# 01_Power.net
KiCad netlist of a schematic drawn in Altium Designer
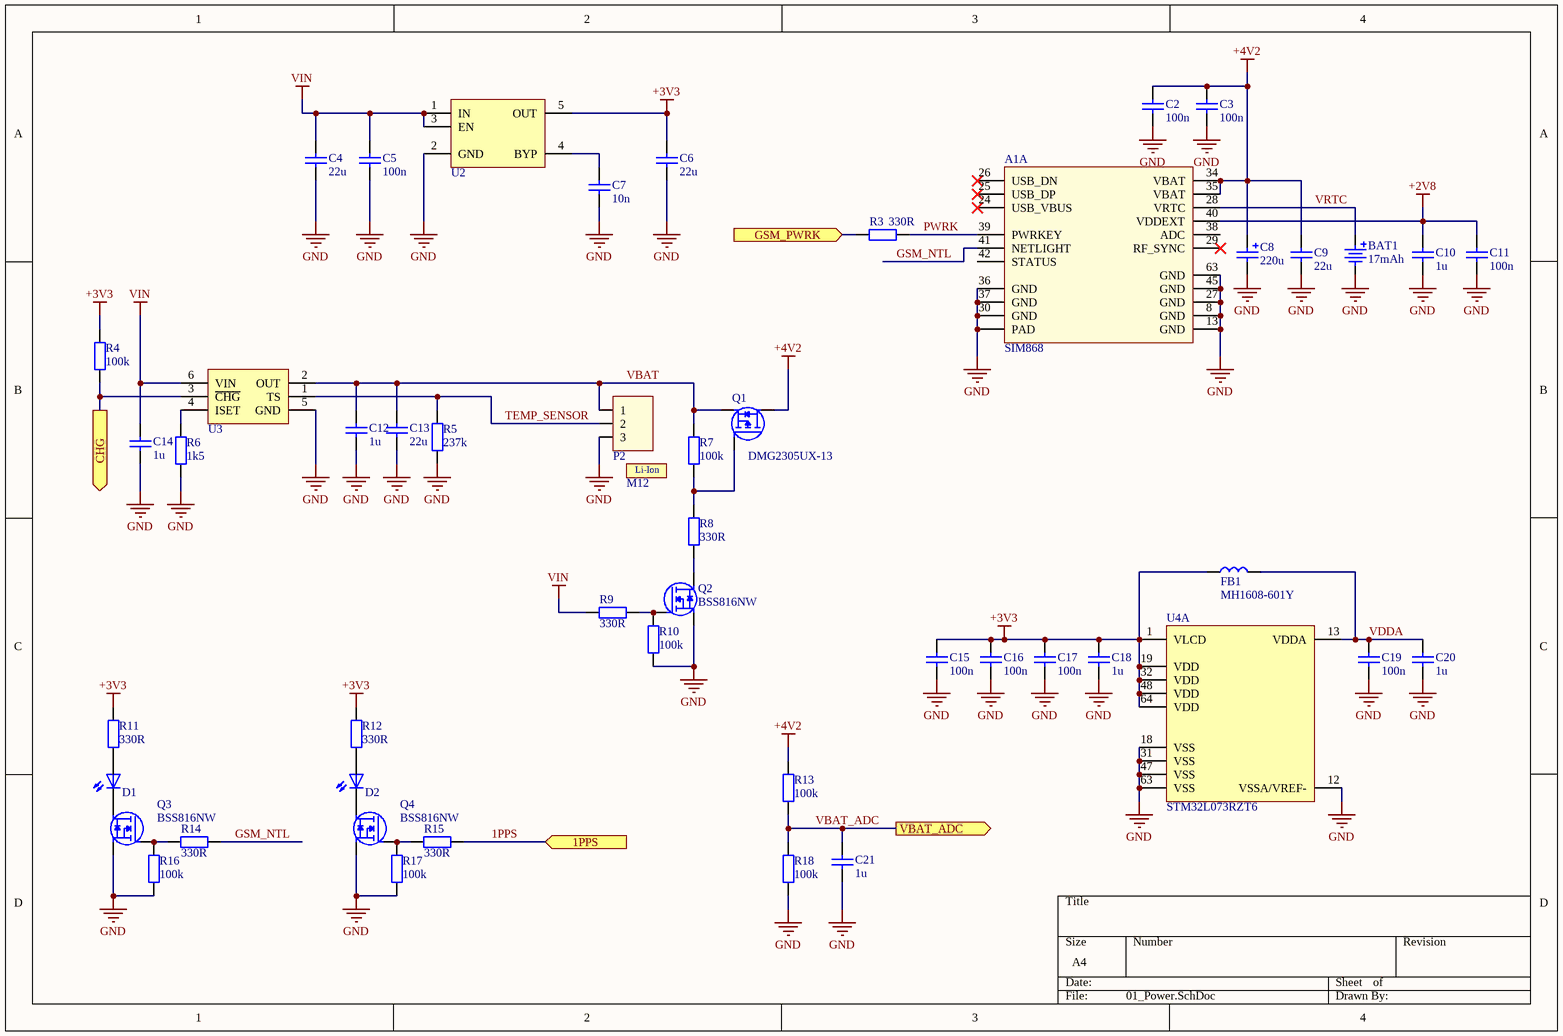
[diagram p0: 01_Power.SchDoc]

(export (version "E")
  (design (tool "Eeschema 10.0.6"))
  (components
    (comp (ref "A1")
      (value "SIM868")
      (footprint "SIM868")
      (description "GSM & GPRS & GPS Modules PCBModule RoHS")
      (fields (field (name "MANUFACTURER") "SIMCom Wireless Solutions"))
      (libsource (lib "alfasat_lib") (part "SIM868"))
    )
    (comp (ref "BAT1")
      (value "17mAh")
      (footprint "ML1220")
      (description "BATT LITH 3V 17MAH COIN 12.5MM")
      (fields (field (name "MANUFACTURER") "China") (field (name "MANUFACTURER PART NUMBER") "ML1220"))
      (libsource (lib "alfasat_lib") (part "ML1220"))
    )
    (comp (ref "C2")
      (value "100n")
      (footprint "C0603_IPC_MD")
      (description "CAP CER 0.1UF 16V X7R 0603")
      (fields
        (field (name "MANUFACTURER") "Samsung Electro-Mechanics")
        (field (name "MANUFACTURER PART NUMBER") "CL10B104KO8NNNC")
      )
      (libsource (lib "alfasat_lib") (part "CL10B104KO8NNNC"))
    )
    (comp (ref "C3")
      (value "100n")
      (footprint "C0603_IPC_MD")
      (description "CAP CER 0.1UF 16V X7R 0603")
      (fields
        (field (name "MANUFACTURER") "Samsung Electro-Mechanics")
        (field (name "MANUFACTURER PART NUMBER") "CL10B104KO8NNNC")
      )
      (libsource (lib "alfasat_lib") (part "CL10B104KO8NNNC"))
    )
    (comp (ref "C4")
      (value "22u")
      (footprint "C0805_IPC_HD")
      (description "CAP CER 22UF 16V X5R 0805")
      (fields
        (field (name "MANUFACTURER") "Samsung Electro-Mechanics")
        (field (name "MANUFACTURER PART NUMBER") "CL21A226MOCLRNC")
      )
      (libsource (lib "alfasat_lib") (part "CL21A226MOCLRNC"))
    )
    (comp (ref "C5")
      (value "100n")
      (footprint "C0603_IPC_MD")
      (description "CAP CER 0.1UF 16V X7R 0603")
      (fields
        (field (name "MANUFACTURER") "Samsung Electro-Mechanics")
        (field (name "MANUFACTURER PART NUMBER") "CL10B104KO8NNNC")
      )
      (libsource (lib "alfasat_lib") (part "CL10B104KO8NNNC"))
    )
    (comp (ref "C6")
      (value "22u")
      (footprint "C0805_IPC_HD")
      (description "CAP CER 22UF 16V X5R 0805")
      (fields
        (field (name "MANUFACTURER") "Samsung Electro-Mechanics")
        (field (name "MANUFACTURER PART NUMBER") "CL21A226MOCLRNC")
      )
      (libsource (lib "alfasat_lib") (part "CL21A226MOCLRNC"))
    )
    (comp (ref "C7")
      (value "10n")
      (footprint "C0603_IPC_MD")
      (description "CAP CER 0.01UF 50V X7R 0603")
      (fields
        (field (name "MANUFACTURER") "Samsung Electro-Mechanics")
        (field (name "MANUFACTURER PART NUMBER") "CL10B103KB8NNNC")
      )
      (libsource (lib "alfasat_lib") (part "CL10B103KB8NNNC"))
    )
    (comp (ref "C8")
      (value "220u")
      (footprint "TANT_CAP_7343")
      (description "Tantalum Capacitors 220uF 6.3V CASE-D_7343 RoHS")
      (fields (field (name "MANUFACTURER") "PANASONIC") (field (name "MANUFACTURER PART NUMBER") "6TPE220MI"))
      (libsource (lib "alfasat_lib") (part "6TPE220MI"))
    )
    (comp (ref "C9")
      (value "22u")
      (footprint "C0805_IPC_HD")
      (description "CAP CER 22UF 16V X5R 0805")
      (fields
        (field (name "MANUFACTURER") "Samsung Electro-Mechanics")
        (field (name "MANUFACTURER PART NUMBER") "CL21A226MOCLRNC")
      )
      (libsource (lib "alfasat_lib") (part "CL21A226MOCLRNC"))
    )
    (comp (ref "C10")
      (value "1u")
      (footprint "C0603_IPC_MD")
      (description "CAP CER 1UF 16V X7R 0603")
      (fields
        (field (name "MANUFACTURER") "Samsung Electro-Mechanics")
        (field (name "MANUFACTURER PART NUMBER") "CL10B105MO8NNWC")
      )
      (libsource (lib "alfasat_lib") (part "CL10B105MO8NNWC"))
    )
    (comp (ref "C11")
      (value "100n")
      (footprint "C0603_IPC_MD")
      (description "CAP CER 0.1UF 16V X7R 0603")
      (fields
        (field (name "MANUFACTURER") "Samsung Electro-Mechanics")
        (field (name "MANUFACTURER PART NUMBER") "CL10B104KO8NNNC")
      )
      (libsource (lib "alfasat_lib") (part "CL10B104KO8NNNC"))
    )
    (comp (ref "C12")
      (value "1u")
      (footprint "C0603_IPC_MD")
      (description "CAP CER 1UF 16V X7R 0603")
      (fields
        (field (name "MANUFACTURER") "Samsung Electro-Mechanics")
        (field (name "MANUFACTURER PART NUMBER") "CL10B105MO8NNWC")
      )
      (libsource (lib "alfasat_lib") (part "CL10B105MO8NNWC"))
    )
    (comp (ref "C13")
      (value "22u")
      (footprint "C0805_IPC_HD")
      (description "CAP CER 22UF 16V X5R 0805")
      (fields
        (field (name "MANUFACTURER") "Samsung Electro-Mechanics")
        (field (name "MANUFACTURER PART NUMBER") "CL21A226MOCLRNC")
      )
      (libsource (lib "alfasat_lib") (part "CL21A226MOCLRNC"))
    )
    (comp (ref "C14")
      (value "1u")
      (footprint "C0603_IPC_MD")
      (description "CAP CER 1UF 16V X7R 0603")
      (fields
        (field (name "MANUFACTURER") "Samsung Electro-Mechanics")
        (field (name "MANUFACTURER PART NUMBER") "CL10B105MO8NNWC")
      )
      (libsource (lib "alfasat_lib") (part "CL10B105MO8NNWC"))
    )
    (comp (ref "C15")
      (value "100n")
      (footprint "C0603_IPC_MD")
      (description "CAP CER 0.1UF 16V X7R 0603")
      (fields
        (field (name "MANUFACTURER") "Samsung Electro-Mechanics")
        (field (name "MANUFACTURER PART NUMBER") "CL10B104KO8NNNC")
      )
      (libsource (lib "alfasat_lib") (part "CL10B104KO8NNNC"))
    )
    (comp (ref "C16")
      (value "100n")
      (footprint "C0603_IPC_MD")
      (description "CAP CER 0.1UF 16V X7R 0603")
      (fields
        (field (name "MANUFACTURER") "Samsung Electro-Mechanics")
        (field (name "MANUFACTURER PART NUMBER") "CL10B104KO8NNNC")
      )
      (libsource (lib "alfasat_lib") (part "CL10B104KO8NNNC"))
    )
    (comp (ref "C17")
      (value "100n")
      (footprint "C0603_IPC_MD")
      (description "CAP CER 0.1UF 16V X7R 0603")
      (fields
        (field (name "MANUFACTURER") "Samsung Electro-Mechanics")
        (field (name "MANUFACTURER PART NUMBER") "CL10B104KO8NNNC")
      )
      (libsource (lib "alfasat_lib") (part "CL10B104KO8NNNC"))
    )
    (comp (ref "C18")
      (value "1u")
      (footprint "C0603_IPC_MD")
      (description "CAP CER 1UF 16V X7R 0603")
      (fields
        (field (name "MANUFACTURER") "Samsung Electro-Mechanics")
        (field (name "MANUFACTURER PART NUMBER") "CL10B105MO8NNWC")
      )
      (libsource (lib "alfasat_lib") (part "CL10B105MO8NNWC"))
    )
    (comp (ref "C19")
      (value "100n")
      (footprint "C0603_IPC_MD")
      (description "CAP CER 0.1UF 16V X7R 0603")
      (fields
        (field (name "MANUFACTURER") "Samsung Electro-Mechanics")
        (field (name "MANUFACTURER PART NUMBER") "CL10B104KO8NNNC")
      )
      (libsource (lib "alfasat_lib") (part "CL10B104KO8NNNC"))
    )
    (comp (ref "C20")
      (value "1u")
      (footprint "C0603_IPC_MD")
      (description "CAP CER 1UF 16V X7R 0603")
      (fields
        (field (name "MANUFACTURER") "Samsung Electro-Mechanics")
        (field (name "MANUFACTURER PART NUMBER") "CL10B105MO8NNWC")
      )
      (libsource (lib "alfasat_lib") (part "CL10B105MO8NNWC"))
    )
    (comp (ref "C21")
      (value "1u")
      (footprint "C0603_IPC_MD")
      (description "CAP CER 1UF 16V X7R 0603")
      (fields
        (field (name "MANUFACTURER") "Samsung Electro-Mechanics")
        (field (name "MANUFACTURER PART NUMBER") "CL10B105MO8NNWC")
      )
      (libsource (lib "alfasat_parts_lib") (part "CL10B105MO8NNWC"))
    )
    (comp (ref "D1")
      (value "LTL-4231N")
      (footprint "LED3MM_HOLDER")
      (description "Light Emitting Diodes (LED) Green 569nm 12.6mcd@10mA Top View DIP3mm RoHS")
      (fields (field (name "MANUFACTURER") "Lite-On"))
      (libsource (lib "alfasat_lib") (part "LTL-4231N"))
    )
    (comp (ref "D2")
      (value "LTL-4231N")
      (footprint "LED3MM_HOLDER")
      (description "Light Emitting Diodes (LED) Green 569nm 12.6mcd@10mA Top View DIP3mm RoHS")
      (fields (field (name "MANUFACTURER") "Lite-On"))
      (libsource (lib "alfasat_lib") (part "LTL-4231N"))
    )
    (comp (ref "FB1")
      (value "MH1608-601Y")
      (footprint "L0603_IPC_MD")
      (description "FERRITE BEAD 600R@100MHz 0603 for Power Line, 1000mA")
      (fields (field (name "MANUFACTURER") "Bourns Inc."))
      (libsource (lib "alfasat_lib") (part "MH1608-601Y"))
    )
    (comp (ref "M12")
      (value "Li-Ion-1000mAh")
      (description "Nano SimCard")
      (fields (field (name "MANUFACTURER") "China"))
      (libsource (lib "alfasat_lib") (part "Li-Ion-1000mAh"))
    )
    (comp (ref "P2")
      (value "JST_3V_1.25MM")
      (footprint "JST_1.25MM_3V")
      (description "1.25mm Pitch Connector Micro JST Horizontal Straight Pin 3")
      (fields (field (name "MANUFACTURER") "China"))
      (libsource (lib "alfasat_lib") (part "JST_3V_1.25MM"))
    )
    (comp (ref "Q1")
      (value "DMG2305UX-13")
      (footprint "SOT23")
      (description "MOSFET P-CH 20V 4.2A SOT23")
      (fields (field (name "MANUFACTURER") "Diodes Inc."))
      (libsource (lib "alfasat_lib") (part "DMG2305"))
    )
    (comp (ref "Q2")
      (value "BSS816NW")
      (footprint "SOT323")
      (description "N-Channel Logic Level Enhancement Mode Field Effect Transistor")
      (fields (field (name "MANUFACTURER") "Infineon Technologies"))
      (libsource (lib "alfasat_lib") (part "BSS816"))
    )
    (comp (ref "Q3")
      (value "BSS816NW")
      (footprint "SOT323")
      (description "N-Channel Logic Level Enhancement Mode Field Effect Transistor")
      (fields (field (name "MANUFACTURER") "Infineon Technologies"))
      (libsource (lib "alfasat_lib") (part "BSS816"))
    )
    (comp (ref "Q4")
      (value "BSS816NW")
      (footprint "SOT323")
      (description "N-Channel Logic Level Enhancement Mode Field Effect Transistor")
      (fields (field (name "MANUFACTURER") "Infineon Technologies"))
      (libsource (lib "alfasat_lib") (part "BSS816"))
    )
    (comp (ref "R3")
      (value "330R")
      (footprint "R0603_IPC_MD")
      (description "RES SMD 330 OHM 5% 1/10W 0603")
      (fields
        (field (name "MANUFACTURER") "Bourns Inc.")
        (field (name "MANUFACTURER PART NUMBER") "CR0603-JW-331ELF")
      )
      (libsource (lib "alfasat_lib") (part "CR0603-JW-331ELF"))
    )
    (comp (ref "R4")
      (value "100k")
      (footprint "R0603_IPC_MD")
      (description "RES 100K OHM 1% 1/10W 0603")
      (fields
        (field (name "MANUFACTURER") "Bourns Inc.")
        (field (name "MANUFACTURER PART NUMBER") "RMCF0603FT100K")
      )
      (libsource (lib "alfasat_lib") (part "RMCF0603FT100K"))
    )
    (comp (ref "R5")
      (value "237k")
      (footprint "R0603_IPC_MD")
      (description "RES SMD 237K OHM 1% 1/10W 0603")
      (fields
        (field (name "MANUFACTURER") "YAGEO")
        (field (name "MANUFACTURER PART NUMBER") "RC0603FR-07237KL")
      )
      (libsource (lib "alfasat_lib") (part "RC0603FR-07237KL"))
    )
    (comp (ref "R6")
      (value "1k5")
      (footprint "R0603_IPC_MD")
      (description "RES SMD 1.5K OHM 5% 1/10W 0603")
      (fields
        (field (name "MANUFACTURER") "Yageo")
        (field (name "MANUFACTURER PART NUMBER") "RC0603JR-071K5L")
      )
      (libsource (lib "alfasat_lib") (part "RC0603JR-071K5L"))
    )
    (comp (ref "R7")
      (value "100k")
      (footprint "R0603_IPC_MD")
      (description "RES 100K OHM 1% 1/10W 0603")
      (fields
        (field (name "MANUFACTURER") "Bourns Inc.")
        (field (name "MANUFACTURER PART NUMBER") "RMCF0603FT100K")
      )
      (libsource (lib "alfasat_lib") (part "RMCF0603FT100K"))
    )
    (comp (ref "R8")
      (value "330R")
      (footprint "R0603_IPC_MD")
      (description "RES SMD 330 OHM 5% 1/10W 0603")
      (fields
        (field (name "MANUFACTURER") "Bourns Inc.")
        (field (name "MANUFACTURER PART NUMBER") "CR0603-JW-331ELF")
      )
      (libsource (lib "") (part "CR0603-JW-331ELF_2"))
    )
    (comp (ref "R9")
      (value "330R")
      (footprint "R0603_IPC_MD")
      (description "RES SMD 330 OHM 5% 1/10W 0603")
      (fields
        (field (name "MANUFACTURER") "Bourns Inc.")
        (field (name "MANUFACTURER PART NUMBER") "CR0603-JW-331ELF")
      )
      (libsource (lib "") (part "CR0603-JW-331ELF_1"))
    )
    (comp (ref "R10")
      (value "100k")
      (footprint "R0603_IPC_MD")
      (description "RES 100K OHM 1% 1/10W 0603")
      (fields
        (field (name "MANUFACTURER") "Bourns Inc.")
        (field (name "MANUFACTURER PART NUMBER") "RMCF0603FT100K")
      )
      (libsource (lib "") (part "RMCF0603FT100K_1"))
    )
    (comp (ref "R11")
      (value "330R")
      (footprint "R0603_IPC_MD")
      (description "RES SMD 330 OHM 5% 1/10W 0603")
      (fields
        (field (name "MANUFACTURER") "Bourns Inc.")
        (field (name "MANUFACTURER PART NUMBER") "CR0603-JW-331ELF")
      )
      (libsource (lib "") (part "CR0603-JW-331ELF_2"))
    )
    (comp (ref "R12")
      (value "330R")
      (footprint "R0603_IPC_MD")
      (description "RES SMD 330 OHM 5% 1/10W 0603")
      (fields
        (field (name "MANUFACTURER") "Bourns Inc.")
        (field (name "MANUFACTURER PART NUMBER") "CR0603-JW-331ELF")
      )
      (libsource (lib "") (part "CR0603-JW-331ELF_2"))
    )
    (comp (ref "R13")
      (value "100k")
      (footprint "R0603_IPC_MD")
      (description "RES 100K OHM 1% 1/10W 0603")
      (fields
        (field (name "MANUFACTURER") "Bourns Inc.")
        (field (name "MANUFACTURER PART NUMBER") "RMCF0603FT100K")
      )
      (libsource (lib "alfasat_parts_lib") (part "RMCF0603FT100K"))
    )
    (comp (ref "R14")
      (value "330R")
      (footprint "R0603_IPC_MD")
      (description "RES SMD 330 OHM 5% 1/10W 0603")
      (fields
        (field (name "MANUFACTURER") "Bourns Inc.")
        (field (name "MANUFACTURER PART NUMBER") "CR0603-JW-331ELF")
      )
      (libsource (lib "alfasat_lib") (part "CR0603-JW-331ELF"))
    )
    (comp (ref "R15")
      (value "330R")
      (footprint "R0603_IPC_MD")
      (description "RES SMD 330 OHM 5% 1/10W 0603")
      (fields
        (field (name "MANUFACTURER") "Bourns Inc.")
        (field (name "MANUFACTURER PART NUMBER") "CR0603-JW-331ELF")
      )
      (libsource (lib "alfasat_lib") (part "CR0603-JW-331ELF"))
    )
    (comp (ref "R16")
      (value "100k")
      (footprint "R0603_IPC_MD")
      (description "RES 100K OHM 1% 1/10W 0603")
      (fields
        (field (name "MANUFACTURER") "Bourns Inc.")
        (field (name "MANUFACTURER PART NUMBER") "RMCF0603FT100K")
      )
      (libsource (lib "alfasat_lib") (part "RMCF0603FT100K"))
    )
    (comp (ref "R17")
      (value "100k")
      (footprint "R0603_IPC_MD")
      (description "RES 100K OHM 1% 1/10W 0603")
      (fields
        (field (name "MANUFACTURER") "Bourns Inc.")
        (field (name "MANUFACTURER PART NUMBER") "RMCF0603FT100K")
      )
      (libsource (lib "alfasat_lib") (part "RMCF0603FT100K"))
    )
    (comp (ref "R18")
      (value "100k")
      (footprint "R0603_IPC_MD")
      (description "RES 100K OHM 1% 1/10W 0603")
      (fields
        (field (name "MANUFACTURER") "Bourns Inc.")
        (field (name "MANUFACTURER PART NUMBER") "RMCF0603FT100K")
      )
      (libsource (lib "alfasat_parts_lib") (part "RMCF0603FT100K"))
    )
    (comp (ref "U2")
      (value "MIC5219-3.3YM5-TR")
      (footprint "SOT23-5_(MT)")
      (description "IC REG LINEAR 3.3V 500MA SOT23-5")
      (fields (field (name "MANUFACTURER") "Microchip Technology"))
      (libsource (lib "alfasat_lib") (part "MIC5219-3.3YM5-TR"))
    )
    (comp (ref "U3")
      (value "BQ21040DBVR")
      (footprint "SOT23-6")
      (description "IC BAT CHG LI-ION 1 CELL SOT23-6")
      (fields (field (name "MANUFACTURER") "Texas Instruments"))
      (libsource (lib "alfasat_lib") (part "BQ21040DBVR"))
    )
    (comp (ref "U4")
      (value "STM32L073RZT6")
      (footprint "LQFP64_10X10MM")
      (description "Ultra-low-power 32-bit MCU ARM®-based Cortex®-M0+")
      (fields (field (name "MANUFACTURER") "ST"))
      (libsource (lib "alfasat_lib") (part "STM32L073RZT6"))
    )
  )
  (nets
    (net (code "1") (name "+2V8") (class "Default")
      (node (ref "A1") (pin "40") (pinfunction "VDDEXT_40") (pintype "passive"))
      (node (ref "C10") (pin "2") (pinfunction "2_2") (pintype "passive"))
      (node (ref "C11") (pin "2") (pinfunction "2_2") (pintype "passive"))
    )
    (net (code "2") (name "+3V3") (class "Default")
      (node (ref "C15") (pin "2") (pinfunction "2_2") (pintype "passive"))
      (node (ref "C16") (pin "2") (pinfunction "2_2") (pintype "passive"))
      (node (ref "C17") (pin "2") (pinfunction "2_2") (pintype "passive"))
      (node (ref "C18") (pin "2") (pinfunction "2_2") (pintype "passive"))
      (node (ref "C6") (pin "1") (pinfunction "1_1") (pintype "passive"))
      (node (ref "FB1") (pin "1") (pinfunction "1_1") (pintype "passive"))
      (node (ref "R11") (pin "2") (pinfunction "2_2") (pintype "passive"))
      (node (ref "R12") (pin "2") (pinfunction "2_2") (pintype "passive"))
      (node (ref "R4") (pin "2") (pinfunction "2_2") (pintype "passive"))
      (node (ref "U2") (pin "5") (pinfunction "OUT_5") (pintype "passive"))
      (node (ref "U4") (pin "1") (pinfunction "VLCD_1") (pintype "power_in"))
      (node (ref "U4") (pin "19") (pinfunction "VDD_19") (pintype "power_in"))
      (node (ref "U4") (pin "32") (pinfunction "VDD_32") (pintype "power_in"))
      (node (ref "U4") (pin "48") (pinfunction "VDD_48") (pintype "power_in"))
      (node (ref "U4") (pin "64") (pinfunction "VDD_64") (pintype "power_in"))
    )
    (net (code "3") (name "+4V2") (class "Default")
      (node (ref "A1") (pin "34") (pinfunction "VBAT_34") (pintype "power_in"))
      (node (ref "A1") (pin "35") (pinfunction "VBAT_35") (pintype "power_in"))
      (node (ref "C2") (pin "2") (pinfunction "2_2") (pintype "passive"))
      (node (ref "C3") (pin "2") (pinfunction "2_2") (pintype "passive"))
      (node (ref "C8") (pin "1") (pinfunction "1_1") (pintype "passive"))
      (node (ref "C9") (pin "1") (pinfunction "1_1") (pintype "passive"))
      (node (ref "Q1") (pin "3") (pinfunction "D_3") (pintype "passive"))
      (node (ref "R13") (pin "2") (pinfunction "2_2") (pintype "passive"))
    )
    (net (code "4") (name "/1PPS") (class "Default")
      (node (ref "R15") (pin "2") (pinfunction "2_2") (pintype "passive"))
    )
    (net (code "5") (name "/CHG") (class "Default")
      (node (ref "R4") (pin "1") (pinfunction "1_1") (pintype "passive"))
      (node (ref "U3") (pin "3") (pinfunction "~{CHG}_3") (pintype "passive"))
    )
    (net (code "6") (name "/GSM_NTL") (class "Default")
      (node (ref "A1") (pin "41") (pinfunction "NETLIGHT_41") (pintype "passive"))
      (node (ref "R14") (pin "2") (pinfunction "2_2") (pintype "passive"))
    )
    (net (code "7") (name "/GSM_PWRK") (class "Default")
      (node (ref "R3") (pin "1") (pinfunction "1_1") (pintype "passive"))
    )
    (net (code "8") (name "/PWRK") (class "Default")
      (node (ref "A1") (pin "39") (pinfunction "PWRKEY_39") (pintype "passive"))
      (node (ref "R3") (pin "2") (pinfunction "2_2") (pintype "passive"))
    )
    (net (code "9") (name "/TEMP_SENSOR") (class "Default")
      (node (ref "P2") (pin "2") (pinfunction "2_2") (pintype "passive"))
      (node (ref "R5") (pin "2") (pinfunction "2_2") (pintype "passive"))
      (node (ref "U3") (pin "1") (pinfunction "TS_1") (pintype "passive"))
    )
    (net (code "10") (name "/VBAT") (class "Default")
      (node (ref "C12") (pin "2") (pinfunction "2_2") (pintype "passive"))
      (node (ref "C13") (pin "1") (pinfunction "1_1") (pintype "passive"))
      (node (ref "P2") (pin "1") (pinfunction "1_1") (pintype "passive"))
      (node (ref "Q1") (pin "2") (pinfunction "S_2") (pintype "passive"))
      (node (ref "R7") (pin "2") (pinfunction "2_2") (pintype "passive"))
      (node (ref "U3") (pin "2") (pinfunction "OUT_2") (pintype "passive"))
    )
    (net (code "11") (name "/VBAT_ADC") (class "Default")
      (node (ref "C21") (pin "2") (pinfunction "2_2") (pintype "passive"))
      (node (ref "R13") (pin "1") (pinfunction "1_1") (pintype "passive"))
      (node (ref "R18") (pin "2") (pinfunction "2_2") (pintype "passive"))
    )
    (net (code "12") (name "/VDDA") (class "Default")
      (node (ref "C19") (pin "2") (pinfunction "2_2") (pintype "passive"))
      (node (ref "C20") (pin "2") (pinfunction "2_2") (pintype "passive"))
      (node (ref "FB1") (pin "2") (pinfunction "2_2") (pintype "passive"))
      (node (ref "U4") (pin "13") (pinfunction "VDDA_13") (pintype "power_in"))
    )
    (net (code "13") (name "/VRTC") (class "Default")
      (node (ref "A1") (pin "28") (pinfunction "VRTC_28") (pintype "passive"))
      (node (ref "BAT1") (pin "1") (pinfunction "1_1") (pintype "passive"))
    )
    (net (code "14") (name "GND") (class "Default")
      (node (ref "A1") (pin "13") (pinfunction "GND_13") (pintype "passive"))
      (node (ref "A1") (pin "27") (pinfunction "GND_27") (pintype "passive"))
      (node (ref "A1") (pin "30") (pinfunction "GND_30") (pintype "passive"))
      (node (ref "A1") (pin "36") (pinfunction "GND_36") (pintype "passive"))
      (node (ref "A1") (pin "37") (pinfunction "GND_37") (pintype "passive"))
      (node (ref "A1") (pin "45") (pinfunction "GND_45") (pintype "passive"))
      (node (ref "A1") (pin "63") (pinfunction "GND_63") (pintype "passive"))
      (node (ref "A1") (pin "8") (pinfunction "GND_8") (pintype "passive"))
      (node (ref "A1") (pin "PAD") (pinfunction "PAD_PAD") (pintype "passive"))
      (node (ref "BAT1") (pin "2") (pinfunction "2_2") (pintype "passive"))
      (node (ref "C10") (pin "1") (pinfunction "1_1") (pintype "passive"))
      (node (ref "C11") (pin "1") (pinfunction "1_1") (pintype "passive"))
      (node (ref "C12") (pin "1") (pinfunction "1_1") (pintype "passive"))
      (node (ref "C13") (pin "2") (pinfunction "2_2") (pintype "passive"))
      (node (ref "C14") (pin "1") (pinfunction "1_1") (pintype "passive"))
      (node (ref "C15") (pin "1") (pinfunction "1_1") (pintype "passive"))
      (node (ref "C16") (pin "1") (pinfunction "1_1") (pintype "passive"))
      (node (ref "C17") (pin "1") (pinfunction "1_1") (pintype "passive"))
      (node (ref "C18") (pin "1") (pinfunction "1_1") (pintype "passive"))
      (node (ref "C19") (pin "1") (pinfunction "1_1") (pintype "passive"))
      (node (ref "C2") (pin "1") (pinfunction "1_1") (pintype "passive"))
      (node (ref "C20") (pin "1") (pinfunction "1_1") (pintype "passive"))
      (node (ref "C21") (pin "1") (pinfunction "1_1") (pintype "passive"))
      (node (ref "C3") (pin "1") (pinfunction "1_1") (pintype "passive"))
      (node (ref "C4") (pin "2") (pinfunction "2_2") (pintype "passive"))
      (node (ref "C5") (pin "2") (pinfunction "2_2") (pintype "passive"))
      (node (ref "C6") (pin "2") (pinfunction "2_2") (pintype "passive"))
      (node (ref "C7") (pin "1") (pinfunction "1_1") (pintype "passive"))
      (node (ref "C8") (pin "2") (pinfunction "2_2") (pintype "passive"))
      (node (ref "C9") (pin "2") (pinfunction "2_2") (pintype "passive"))
      (node (ref "P2") (pin "3") (pinfunction "3_3") (pintype "passive"))
      (node (ref "Q2") (pin "2") (pinfunction "S_2") (pintype "passive"))
      (node (ref "Q3") (pin "2") (pinfunction "S_2") (pintype "passive"))
      (node (ref "Q4") (pin "2") (pinfunction "S_2") (pintype "passive"))
      (node (ref "R10") (pin "1") (pinfunction "1_1") (pintype "passive"))
      (node (ref "R16") (pin "1") (pinfunction "1_1") (pintype "passive"))
      (node (ref "R17") (pin "1") (pinfunction "1_1") (pintype "passive"))
      (node (ref "R18") (pin "1") (pinfunction "1_1") (pintype "passive"))
      (node (ref "R5") (pin "1") (pinfunction "1_1") (pintype "passive"))
      (node (ref "R6") (pin "1") (pinfunction "1_1") (pintype "passive"))
      (node (ref "U2") (pin "2") (pinfunction "GND_2") (pintype "passive"))
      (node (ref "U3") (pin "5") (pinfunction "GND_5") (pintype "passive"))
      (node (ref "U4") (pin "12") (pinfunction "VSSA/VREF-_12") (pintype "power_in"))
      (node (ref "U4") (pin "18") (pinfunction "VSS_18") (pintype "power_in"))
      (node (ref "U4") (pin "31") (pinfunction "VSS_31") (pintype "power_in"))
      (node (ref "U4") (pin "47") (pinfunction "VSS_47") (pintype "power_in"))
      (node (ref "U4") (pin "63") (pinfunction "VSS_63") (pintype "power_in"))
    )
    (net (code "15") (name "Net-(D1-A)") (class "Default")
      (node (ref "D1") (pin "2") (pinfunction "A_2") (pintype "passive"))
      (node (ref "R11") (pin "1") (pinfunction "1_1") (pintype "passive"))
    )
    (net (code "16") (name "Net-(D1-C)") (class "Default")
      (node (ref "D1") (pin "1") (pinfunction "C_1") (pintype "passive"))
      (node (ref "Q3") (pin "3") (pinfunction "D_3") (pintype "passive"))
    )
    (net (code "17") (name "Net-(D2-A)") (class "Default")
      (node (ref "D2") (pin "2") (pinfunction "A_2") (pintype "passive"))
      (node (ref "R12") (pin "1") (pinfunction "1_1") (pintype "passive"))
    )
    (net (code "18") (name "Net-(D2-C)") (class "Default")
      (node (ref "D2") (pin "1") (pinfunction "C_1") (pintype "passive"))
      (node (ref "Q4") (pin "3") (pinfunction "D_3") (pintype "passive"))
    )
    (net (code "19") (name "Net-(Q1-G)") (class "Default")
      (node (ref "Q1") (pin "1") (pinfunction "G_1") (pintype "passive"))
      (node (ref "R7") (pin "1") (pinfunction "1_1") (pintype "passive"))
      (node (ref "R8") (pin "2") (pinfunction "2_2") (pintype "passive"))
    )
    (net (code "20") (name "Net-(Q2-D)") (class "Default")
      (node (ref "Q2") (pin "3") (pinfunction "D_3") (pintype "passive"))
      (node (ref "R8") (pin "1") (pinfunction "1_1") (pintype "passive"))
    )
    (net (code "21") (name "Net-(Q2-G)") (class "Default")
      (node (ref "Q2") (pin "1") (pinfunction "G_1") (pintype "passive"))
      (node (ref "R10") (pin "2") (pinfunction "2_2") (pintype "passive"))
      (node (ref "R9") (pin "1") (pinfunction "1_1") (pintype "passive"))
    )
    (net (code "22") (name "Net-(Q3-G)") (class "Default")
      (node (ref "Q3") (pin "1") (pinfunction "G_1") (pintype "passive"))
      (node (ref "R14") (pin "1") (pinfunction "1_1") (pintype "passive"))
      (node (ref "R16") (pin "2") (pinfunction "2_2") (pintype "passive"))
    )
    (net (code "23") (name "Net-(Q4-G)") (class "Default")
      (node (ref "Q4") (pin "1") (pinfunction "G_1") (pintype "passive"))
      (node (ref "R15") (pin "1") (pinfunction "1_1") (pintype "passive"))
      (node (ref "R17") (pin "2") (pinfunction "2_2") (pintype "passive"))
    )
    (net (code "24") (name "Net-(U2-BYP)") (class "Default")
      (node (ref "C7") (pin "2") (pinfunction "2_2") (pintype "passive"))
      (node (ref "U2") (pin "4") (pinfunction "BYP_4") (pintype "passive"))
    )
    (net (code "25") (name "Net-(U3-ISET)") (class "Default")
      (node (ref "R6") (pin "2") (pinfunction "2_2") (pintype "passive"))
      (node (ref "U3") (pin "4") (pinfunction "ISET_4") (pintype "passive"))
    )
    (net (code "26") (name "VIN") (class "Default")
      (node (ref "C14") (pin "2") (pinfunction "2_2") (pintype "passive"))
      (node (ref "C4") (pin "1") (pinfunction "1_1") (pintype "passive"))
      (node (ref "C5") (pin "1") (pinfunction "1_1") (pintype "passive"))
      (node (ref "R9") (pin "2") (pinfunction "2_2") (pintype "passive"))
      (node (ref "U2") (pin "1") (pinfunction "IN_1") (pintype "passive"))
      (node (ref "U2") (pin "3") (pinfunction "EN_3") (pintype "passive"))
      (node (ref "U3") (pin "6") (pinfunction "VIN_6") (pintype "passive"))
    )
    (net (code "27") (name "unconnected-(A1A-ADC-Pad38)") (class "Default")
      (node (ref "A1") (pin "38") (pinfunction "ADC_38") (pintype "passive"))
    )
    (net (code "28") (name "unconnected-(A1A-RF_SYNC-Pad29)") (class "Default")
      (node (ref "A1") (pin "29") (pinfunction "RF_SYNC_29") (pintype "passive+no_connect"))
    )
    (net (code "29") (name "unconnected-(A1A-STATUS-Pad42)") (class "Default")
      (node (ref "A1") (pin "42") (pinfunction "STATUS_42") (pintype "passive"))
    )
    (net (code "30") (name "unconnected-(A1A-USB_DN-Pad26)") (class "Default")
      (node (ref "A1") (pin "26") (pinfunction "USB_DN_26") (pintype "passive+no_connect"))
    )
    (net (code "31") (name "unconnected-(A1A-USB_DP-Pad25)") (class "Default")
      (node (ref "A1") (pin "25") (pinfunction "USB_DP_25") (pintype "passive+no_connect"))
    )
    (net (code "32") (name "unconnected-(A1A-USB_VBUS-Pad24)") (class "Default")
      (node (ref "A1") (pin "24") (pinfunction "USB_VBUS_24") (pintype "passive+no_connect"))
    )
  )
)
